# PiZeroGPSHat.net
KiCad netlist of a schematic drawn in EAGLE
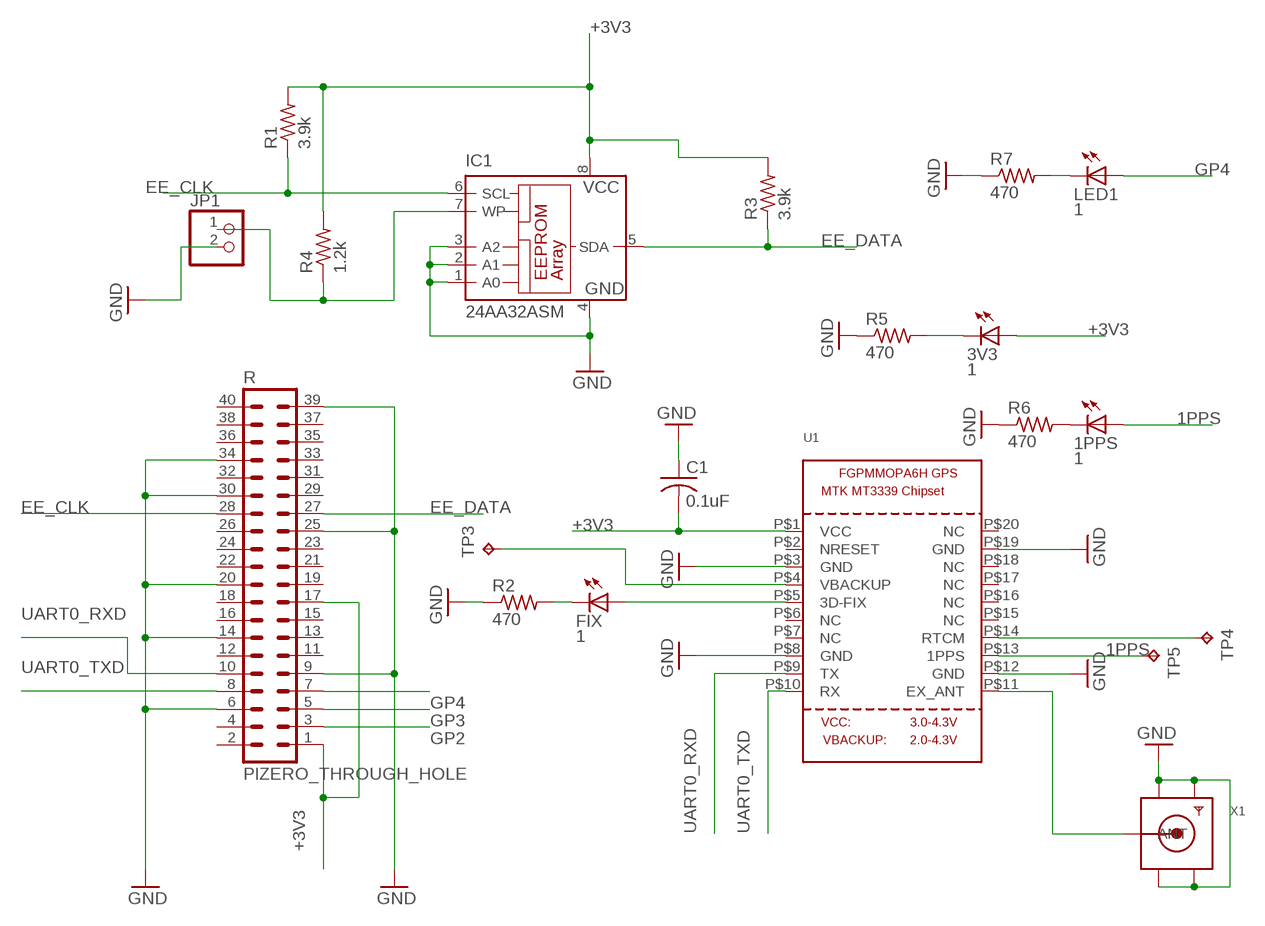
[diagram p0: schematic, sheet 1]

(export (version "E")
  (design (tool "Eeschema 10.0.6"))
  (components
    (comp (ref "1PPS")
      (value "1")
      (footprint "eagle-import:CHIPLED_0805")
      (libsource (lib "eagle-import") (part "LEDCHIPLED_0805"))
    )
    (comp (ref "3V3")
      (value "1")
      (footprint "eagle-import:CHIPLED_0805")
      (libsource (lib "eagle-import") (part "LEDCHIPLED_0805"))
    )
    (comp (ref "C1")
      (value "0.1uF")
      (footprint "eagle-import:C0402")
      (libsource (lib "eagle-import") (part "C-USC0402"))
    )
    (comp (ref "FIX")
      (value "1")
      (footprint "eagle-import:CHIPLED_0805")
      (libsource (lib "eagle-import") (part "LEDCHIPLED_0805"))
    )
    (comp (ref "IC1")
      (value "24AA32ASM")
      (footprint "eagle-import:SO-08M")
      (fields (field (name "MF") "MICROCHIP") (field (name "MPN") "24AA32A-I/SN"))
      (libsource (lib "eagle-import") (part "24SMAA32A"))
    )
    (comp (ref "JP1")
      (value "PINHD-1X2")
      (footprint "eagle-import:1X02")
      (libsource (lib "eagle-import") (part "PINHD-1X2"))
    )
    (comp (ref "LED1")
      (value "1")
      (footprint "eagle-import:CHIPLED_0805")
      (libsource (lib "eagle-import") (part "LEDCHIPLED_0805"))
    )
    (comp (ref "R")
      (value "PIZERO_THROUGH_HOLE")
      (footprint "eagle-import:PIZERO_THOUGH_HOLE")
      (libsource (lib "eagle-import") (part "PIZERO_THROUGH_HOLE"))
    )
    (comp (ref "R1")
      (value "3.9k")
      (footprint "eagle-import:R0402")
      (libsource (lib "eagle-import") (part "R-US_R0402"))
    )
    (comp (ref "R2")
      (value "470")
      (footprint "eagle-import:R0402")
      (libsource (lib "eagle-import") (part "R-US_R0402"))
    )
    (comp (ref "R3")
      (value "3.9k")
      (footprint "eagle-import:R0402")
      (libsource (lib "eagle-import") (part "R-US_R0402"))
    )
    (comp (ref "R4")
      (value "1.2k")
      (footprint "eagle-import:R0402")
      (libsource (lib "eagle-import") (part "R-US_R0402"))
    )
    (comp (ref "R5")
      (value "470")
      (footprint "eagle-import:R0402")
      (libsource (lib "eagle-import") (part "R-US_R0402"))
    )
    (comp (ref "R6")
      (value "470")
      (footprint "eagle-import:R0402")
      (libsource (lib "eagle-import") (part "R-US_R0402"))
    )
    (comp (ref "R7")
      (value "470")
      (footprint "eagle-import:R0402")
      (libsource (lib "eagle-import") (part "R-US_R0402"))
    )
    (comp (ref "TP3")
      (value "TPB1,27")
      (footprint "eagle-import:B1,27")
      (libsource (lib "eagle-import") (part "TPB1,27"))
    )
    (comp (ref "TP4")
      (value "TPB1,27")
      (footprint "eagle-import:B1,27")
      (libsource (lib "eagle-import") (part "TPB1,27"))
    )
    (comp (ref "TP5")
      (value "TPB1,27")
      (footprint "eagle-import:B1,27")
      (libsource (lib "eagle-import") (part "TPB1,27"))
    )
    (comp (ref "U1")
      (value "GPS_FGPMMOPA6H")
      (footprint "eagle-import:FGPMMOPA6H")
      (libsource (lib "eagle-import") (part "GPS_FGPMMOPA6H"))
    )
    (comp (ref "X1")
      (value "SMACONNECTOR")
      (footprint "eagle-import:SMA90_DIP")
      (libsource (lib "eagle-import") (part "SMACONNECTOR"))
    )
  )
  (nets
    (net (code "1") (name "/+3V3") (class "Default")
      (node (ref "3V3") (pin "A") (pinfunction "A_A") (pintype "passive"))
      (node (ref "C1") (pin "2") (pinfunction "2_2") (pintype "passive"))
      (node (ref "IC1") (pin "8") (pinfunction "VCC_8") (pintype "power_in"))
      (node (ref "R") (pin "1") (pinfunction "1_1") (pintype "passive"))
      (node (ref "R") (pin "17") (pinfunction "17_17") (pintype "passive"))
      (node (ref "R1") (pin "2") (pinfunction "2_2") (pintype "passive"))
      (node (ref "R3") (pin "2") (pinfunction "2_2") (pintype "passive"))
      (node (ref "R4") (pin "2") (pinfunction "2_2") (pintype "passive"))
      (node (ref "U1") (pin "P$1") (pinfunction "VCC_P$1") (pintype "bidirectional"))
    )
    (net (code "2") (name "/1PPS") (class "Default")
      (node (ref "1PPS") (pin "A") (pinfunction "A_A") (pintype "passive"))
      (node (ref "TP5") (pin "TP") (pinfunction "TP_TP") (pintype "input"))
      (node (ref "U1") (pin "P$13") (pinfunction "1PPS_P$13") (pintype "bidirectional"))
    )
    (net (code "3") (name "/EE_CLK") (class "Default")
      (node (ref "IC1") (pin "6") (pinfunction "SCL_6") (pintype "input"))
      (node (ref "R") (pin "28") (pinfunction "28_28") (pintype "passive"))
      (node (ref "R1") (pin "1") (pinfunction "1_1") (pintype "passive"))
    )
    (net (code "4") (name "/EE_DATA") (class "Default")
      (node (ref "IC1") (pin "5") (pinfunction "SDA_5") (pintype "bidirectional"))
      (node (ref "R") (pin "27") (pinfunction "27_27") (pintype "passive"))
      (node (ref "R3") (pin "1") (pinfunction "1_1") (pintype "passive"))
    )
    (net (code "5") (name "/GP2") (class "Default")
      (node (ref "R") (pin "3") (pinfunction "3_3") (pintype "passive"))
    )
    (net (code "6") (name "/GP3") (class "Default")
      (node (ref "R") (pin "5") (pinfunction "5_5") (pintype "passive"))
    )
    (net (code "7") (name "/GP4") (class "Default")
      (node (ref "LED1") (pin "A") (pinfunction "A_A") (pintype "passive"))
      (node (ref "R") (pin "7") (pinfunction "7_7") (pintype "passive"))
    )
    (net (code "8") (name "/UART0_RXD") (class "Default")
      (node (ref "R") (pin "10") (pinfunction "10_10") (pintype "passive"))
      (node (ref "U1") (pin "P$9") (pinfunction "TX_P$9") (pintype "bidirectional"))
    )
    (net (code "9") (name "/UART0_TXD") (class "Default")
      (node (ref "R") (pin "8") (pinfunction "8_8") (pintype "passive"))
      (node (ref "U1") (pin "P$10") (pinfunction "RX_P$10") (pintype "bidirectional"))
    )
    (net (code "10") (name "GND") (class "Default")
      (node (ref "C1") (pin "1") (pinfunction "1_1") (pintype "passive"))
      (node (ref "IC1") (pin "1") (pinfunction "A0_1") (pintype "input"))
      (node (ref "IC1") (pin "2") (pinfunction "A1_2") (pintype "input"))
      (node (ref "IC1") (pin "3") (pinfunction "A2_3") (pintype "input"))
      (node (ref "IC1") (pin "4") (pinfunction "GND_4") (pintype "power_in"))
      (node (ref "JP1") (pin "2") (pinfunction "2_2") (pintype "passive"))
      (node (ref "R") (pin "14") (pinfunction "14_14") (pintype "passive"))
      (node (ref "R") (pin "20") (pinfunction "20_20") (pintype "passive"))
      (node (ref "R") (pin "25") (pinfunction "25_25") (pintype "passive"))
      (node (ref "R") (pin "30") (pinfunction "30_30") (pintype "passive"))
      (node (ref "R") (pin "34") (pinfunction "34_34") (pintype "passive"))
      (node (ref "R") (pin "39") (pinfunction "39_39") (pintype "passive"))
      (node (ref "R") (pin "6") (pinfunction "6_6") (pintype "passive"))
      (node (ref "R") (pin "9") (pinfunction "9_9") (pintype "passive"))
      (node (ref "R2") (pin "1") (pinfunction "1_1") (pintype "passive"))
      (node (ref "R5") (pin "1") (pinfunction "1_1") (pintype "passive"))
      (node (ref "R6") (pin "1") (pinfunction "1_1") (pintype "passive"))
      (node (ref "R7") (pin "1") (pinfunction "1_1") (pintype "passive"))
      (node (ref "U1") (pin "P$12") (pinfunction "GND_P$12") (pintype "bidirectional"))
      (node (ref "U1") (pin "P$19") (pinfunction "GND_P$19") (pintype "bidirectional"))
      (node (ref "U1") (pin "P$3") (pinfunction "GND_P$3") (pintype "bidirectional"))
      (node (ref "U1") (pin "P$8") (pinfunction "GND_P$8") (pintype "bidirectional"))
      (node (ref "X1") (pin "GND1") (pinfunction "GND1_GND1") (pintype "power_in"))
      (node (ref "X1") (pin "GND2") (pinfunction "GND2_GND2") (pintype "power_in"))
      (node (ref "X1") (pin "GND3") (pinfunction "GND3_GND3") (pintype "power_in"))
      (node (ref "X1") (pin "GND4") (pinfunction "GND4_GND4") (pintype "power_in"))
    )
    (net (code "11") (name "Net-(1PPS-PadC)") (class "Default")
      (node (ref "1PPS") (pin "C") (pinfunction "C_C") (pintype "passive"))
      (node (ref "R6") (pin "2") (pinfunction "2_2") (pintype "passive"))
    )
    (net (code "12") (name "Net-(3V3-PadC)") (class "Default")
      (node (ref "3V3") (pin "C") (pinfunction "C_C") (pintype "passive"))
      (node (ref "R5") (pin "2") (pinfunction "2_2") (pintype "passive"))
    )
    (net (code "13") (name "Net-(FIX-PadC)") (class "Default")
      (node (ref "FIX") (pin "C") (pinfunction "C_C") (pintype "passive"))
      (node (ref "R2") (pin "2") (pinfunction "2_2") (pintype "passive"))
    )
    (net (code "14") (name "Net-(IC1-WP)") (class "Default")
      (node (ref "IC1") (pin "7") (pinfunction "WP_7") (pintype "input"))
      (node (ref "JP1") (pin "1") (pinfunction "1_1") (pintype "passive"))
      (node (ref "R4") (pin "1") (pinfunction "1_1") (pintype "passive"))
    )
    (net (code "15") (name "Net-(LED1-PadC)") (class "Default")
      (node (ref "LED1") (pin "C") (pinfunction "C_C") (pintype "passive"))
      (node (ref "R7") (pin "2") (pinfunction "2_2") (pintype "passive"))
    )
    (net (code "16") (name "Net-(U1-3D-FIX)") (class "Default")
      (node (ref "FIX") (pin "A") (pinfunction "A_A") (pintype "passive"))
      (node (ref "U1") (pin "P$5") (pinfunction "3D-FIX_P$5") (pintype "bidirectional"))
    )
    (net (code "17") (name "Net-(U1-EX_ANT)") (class "Default")
      (node (ref "U1") (pin "P$11") (pinfunction "EX_ANT_P$11") (pintype "bidirectional"))
      (node (ref "X1") (pin "ANTENNA") (pinfunction "ANT_ANTENNA") (pintype "bidirectional"))
    )
    (net (code "18") (name "Net-(U1-RTCM)") (class "Default")
      (node (ref "TP4") (pin "TP") (pinfunction "TP_TP") (pintype "input"))
      (node (ref "U1") (pin "P$14") (pinfunction "RTCM_P$14") (pintype "bidirectional"))
    )
    (net (code "19") (name "Net-(U1-VBACKUP)") (class "Default")
      (node (ref "TP3") (pin "TP") (pinfunction "TP_TP") (pintype "input"))
      (node (ref "U1") (pin "P$4") (pinfunction "VBACKUP_P$4") (pintype "bidirectional"))
    )
    (net (code "20") (name "unconnected-(R-Pad2)") (class "Default")
      (node (ref "R") (pin "2") (pinfunction "2_2") (pintype "passive"))
    )
    (net (code "21") (name "unconnected-(R-Pad4)") (class "Default")
      (node (ref "R") (pin "4") (pinfunction "4_4") (pintype "passive"))
    )
    (net (code "22") (name "unconnected-(R-Pad11)") (class "Default")
      (node (ref "R") (pin "11") (pinfunction "11_11") (pintype "passive"))
    )
    (net (code "23") (name "unconnected-(R-Pad12)") (class "Default")
      (node (ref "R") (pin "12") (pinfunction "12_12") (pintype "passive"))
    )
    (net (code "24") (name "unconnected-(R-Pad13)") (class "Default")
      (node (ref "R") (pin "13") (pinfunction "13_13") (pintype "passive"))
    )
    (net (code "25") (name "unconnected-(R-Pad15)") (class "Default")
      (node (ref "R") (pin "15") (pinfunction "15_15") (pintype "passive"))
    )
    (net (code "26") (name "unconnected-(R-Pad16)") (class "Default")
      (node (ref "R") (pin "16") (pinfunction "16_16") (pintype "passive"))
    )
    (net (code "27") (name "unconnected-(R-Pad18)") (class "Default")
      (node (ref "R") (pin "18") (pinfunction "18_18") (pintype "passive"))
    )
    (net (code "28") (name "unconnected-(R-Pad19)") (class "Default")
      (node (ref "R") (pin "19") (pinfunction "19_19") (pintype "passive"))
    )
    (net (code "29") (name "unconnected-(R-Pad21)") (class "Default")
      (node (ref "R") (pin "21") (pinfunction "21_21") (pintype "passive"))
    )
    (net (code "30") (name "unconnected-(R-Pad22)") (class "Default")
      (node (ref "R") (pin "22") (pinfunction "22_22") (pintype "passive"))
    )
    (net (code "31") (name "unconnected-(R-Pad23)") (class "Default")
      (node (ref "R") (pin "23") (pinfunction "23_23") (pintype "passive"))
    )
    (net (code "32") (name "unconnected-(R-Pad24)") (class "Default")
      (node (ref "R") (pin "24") (pinfunction "24_24") (pintype "passive"))
    )
    (net (code "33") (name "unconnected-(R-Pad26)") (class "Default")
      (node (ref "R") (pin "26") (pinfunction "26_26") (pintype "passive"))
    )
    (net (code "34") (name "unconnected-(R-Pad29)") (class "Default")
      (node (ref "R") (pin "29") (pinfunction "29_29") (pintype "passive"))
    )
    (net (code "35") (name "unconnected-(R-Pad31)") (class "Default")
      (node (ref "R") (pin "31") (pinfunction "31_31") (pintype "passive"))
    )
    (net (code "36") (name "unconnected-(R-Pad32)") (class "Default")
      (node (ref "R") (pin "32") (pinfunction "32_32") (pintype "passive"))
    )
    (net (code "37") (name "unconnected-(R-Pad33)") (class "Default")
      (node (ref "R") (pin "33") (pinfunction "33_33") (pintype "passive"))
    )
    (net (code "38") (name "unconnected-(R-Pad35)") (class "Default")
      (node (ref "R") (pin "35") (pinfunction "35_35") (pintype "passive"))
    )
    (net (code "39") (name "unconnected-(R-Pad36)") (class "Default")
      (node (ref "R") (pin "36") (pinfunction "36_36") (pintype "passive"))
    )
    (net (code "40") (name "unconnected-(R-Pad37)") (class "Default")
      (node (ref "R") (pin "37") (pinfunction "37_37") (pintype "passive"))
    )
    (net (code "41") (name "unconnected-(R-Pad38)") (class "Default")
      (node (ref "R") (pin "38") (pinfunction "38_38") (pintype "passive"))
    )
    (net (code "42") (name "unconnected-(R-Pad40)") (class "Default")
      (node (ref "R") (pin "40") (pinfunction "40_40") (pintype "passive"))
    )
    (net (code "43") (name "unconnected-(U1-NC-PadP$6)") (class "Default")
      (node (ref "U1") (pin "P$6") (pinfunction "NC_P$6") (pintype "bidirectional"))
    )
    (net (code "44") (name "unconnected-(U1-NC-PadP$7)") (class "Default")
      (node (ref "U1") (pin "P$7") (pinfunction "NC_P$7") (pintype "bidirectional"))
    )
    (net (code "45") (name "unconnected-(U1-NC-PadP$15)") (class "Default")
      (node (ref "U1") (pin "P$15") (pinfunction "NC_P$15") (pintype "bidirectional"))
    )
    (net (code "46") (name "unconnected-(U1-NC-PadP$16)") (class "Default")
      (node (ref "U1") (pin "P$16") (pinfunction "NC_P$16") (pintype "bidirectional"))
    )
    (net (code "47") (name "unconnected-(U1-NC-PadP$17)") (class "Default")
      (node (ref "U1") (pin "P$17") (pinfunction "NC_P$17") (pintype "bidirectional"))
    )
    (net (code "48") (name "unconnected-(U1-NC-PadP$18)") (class "Default")
      (node (ref "U1") (pin "P$18") (pinfunction "NC_P$18") (pintype "bidirectional"))
    )
    (net (code "49") (name "unconnected-(U1-NC-PadP$20)") (class "Default")
      (node (ref "U1") (pin "P$20") (pinfunction "NC_P$20") (pintype "bidirectional"))
    )
    (net (code "50") (name "unconnected-(U1-NRESET-PadP$2)") (class "Default")
      (node (ref "U1") (pin "P$2") (pinfunction "NRESET_P$2") (pintype "bidirectional"))
    )
  )
)
